# audio_jack_passthru.net
KiCad netlist of a schematic drawn in EAGLE
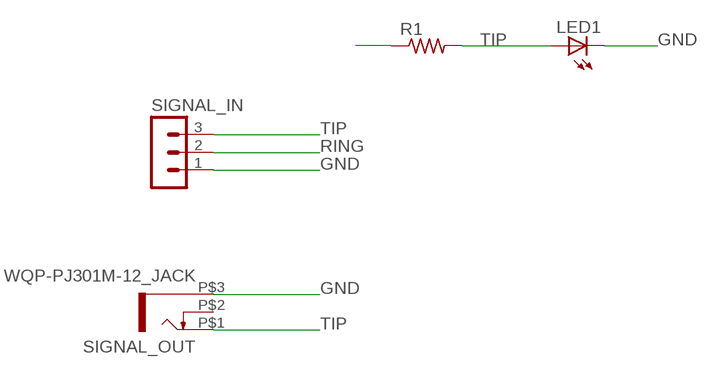
[diagram p0: schematic, sheet 1]

(export (version "E")
  (design (tool "Eeschema 10.0.6"))
  (components
    (comp (ref "LED1")
      (value "LED3MM")
      (footprint "eagle-import:LED3MM")
      (libsource (lib "eagle-import") (part "LED3MM"))
    )
    (comp (ref "R1")
      (value "R-US_R0805")
      (footprint "eagle-import:R0805")
      (libsource (lib "eagle-import") (part "R-US_R0805"))
    )
    (comp (ref "SIGNAL_IN")
      (value "MA03-1")
      (footprint "eagle-import:MA03-1")
      (libsource (lib "eagle-import") (part "MA03-1"))
    )
    (comp (ref "SIGNAL_OUT")
      (value "WQP-PJ301M-12_JACK")
      (footprint "eagle-import:WQP-PJ301M-12_JACK")
      (libsource (lib "eagle-import") (part "WQP-PJ301M-12_JACK"))
    )
  )
  (nets
    (net (code "1") (name "/GND") (class "Default")
      (node (ref "LED1") (pin "K") (pinfunction "C_K") (pintype "passive"))
      (node (ref "SIGNAL_IN") (pin "1") (pinfunction "1_1") (pintype "passive"))
      (node (ref "SIGNAL_OUT") (pin "P$3") (pinfunction "1_P$3") (pintype "passive"))
    )
    (net (code "2") (name "/RING") (class "Default")
      (node (ref "SIGNAL_IN") (pin "2") (pinfunction "2_2") (pintype "passive"))
    )
    (net (code "3") (name "/TIP") (class "Default")
      (node (ref "LED1") (pin "A") (pinfunction "A_A") (pintype "passive"))
      (node (ref "R1") (pin "1") (pinfunction "1_1") (pintype "passive"))
      (node (ref "R1") (pin "2") (pinfunction "2_2") (pintype "passive"))
      (node (ref "SIGNAL_IN") (pin "3") (pinfunction "3_3") (pintype "passive"))
      (node (ref "SIGNAL_OUT") (pin "P$1") (pinfunction "2_P$1") (pintype "passive"))
    )
    (net (code "4") (name "unconnected-(SIGNAL_OUT-3-PadP$2)") (class "Default")
      (node (ref "SIGNAL_OUT") (pin "P$2") (pinfunction "3_P$2") (pintype "passive"))
    )
  )
)
